# LB_BIT_o13_FAN-v03_rev4_4.net
KiCad netlist of a schematic drawn in EAGLE
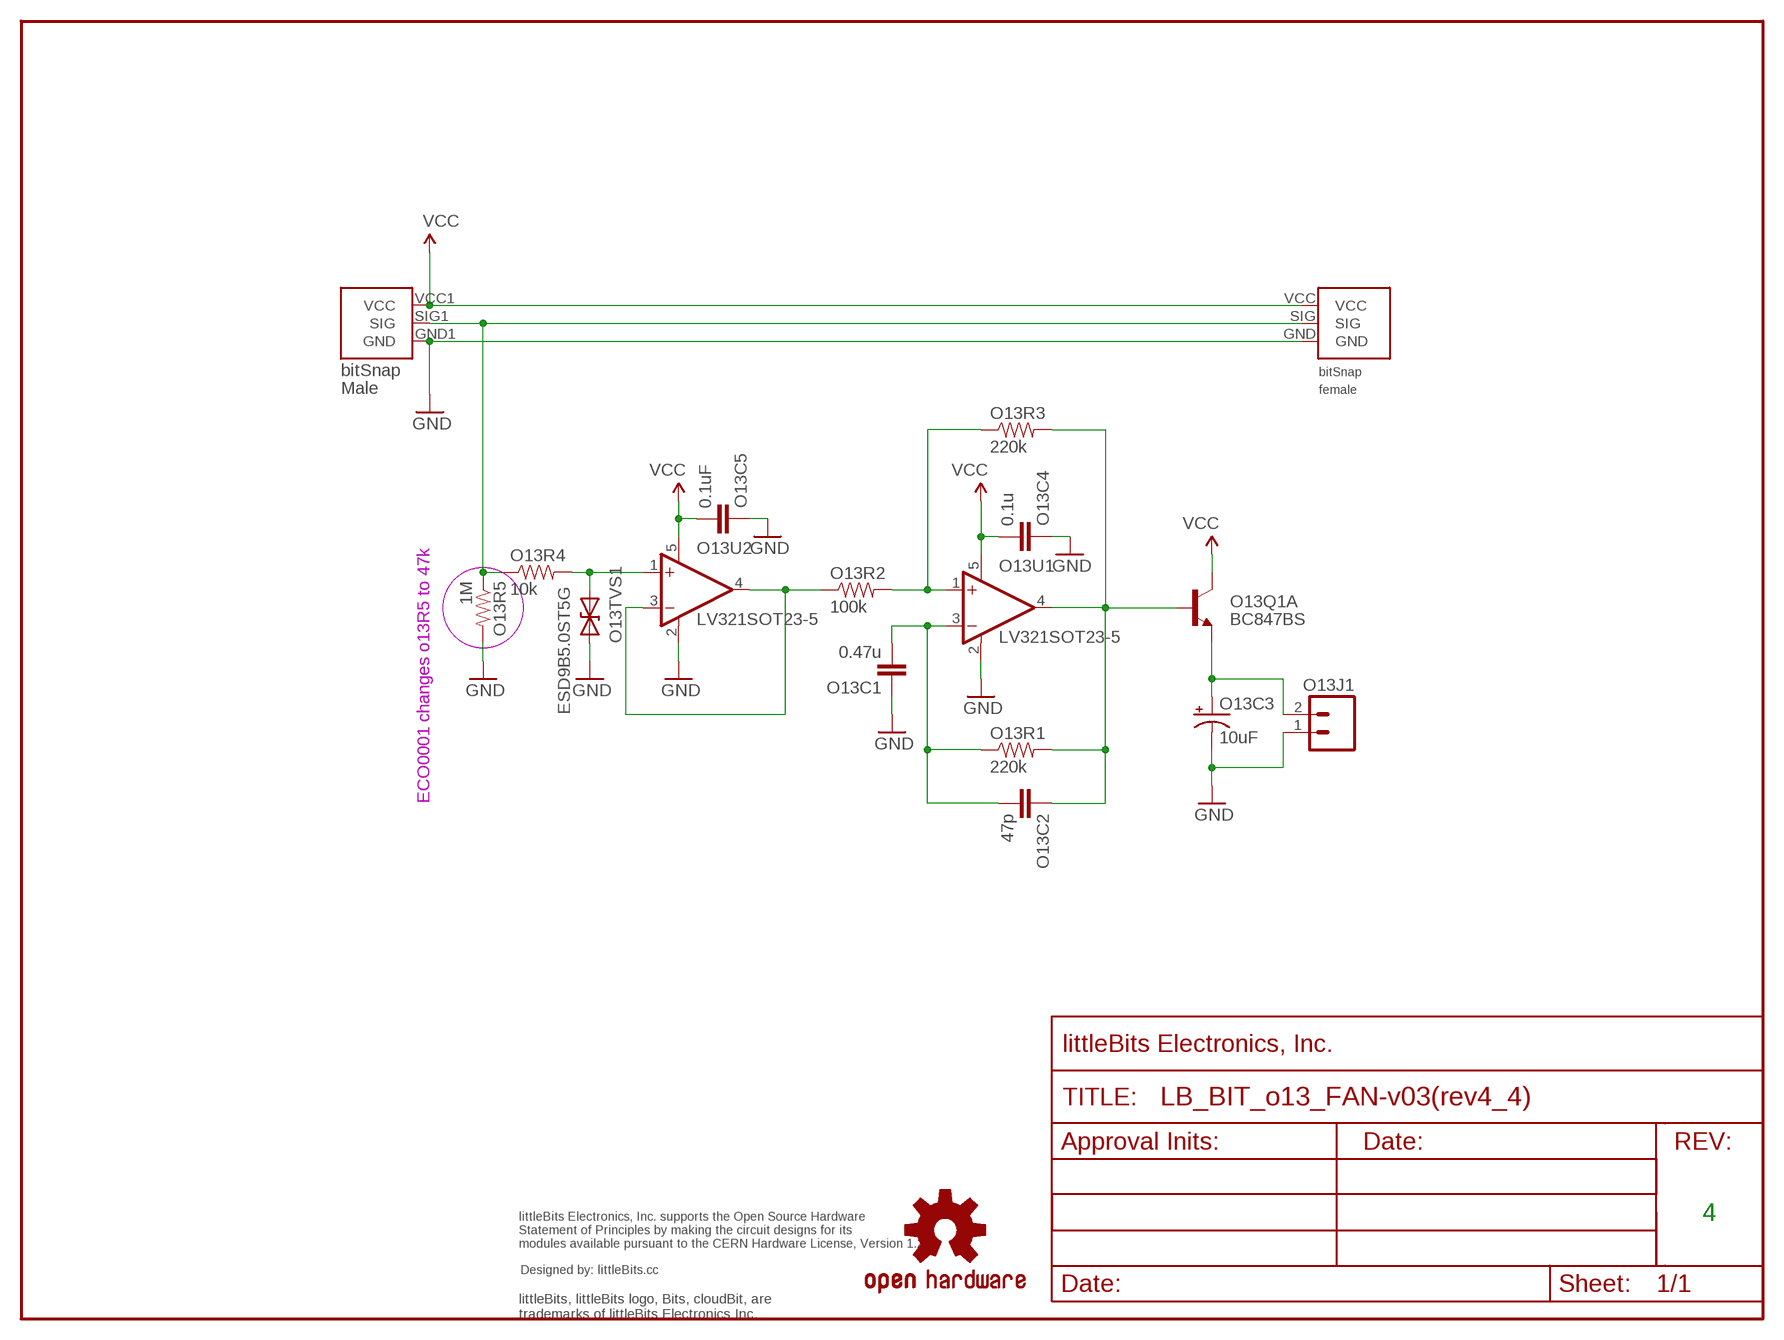
[diagram p0: schematic, sheet 1]

(export (version "E")
  (design (tool "Eeschema 10.0.6"))
  (components
    (comp (ref "O13BSF1")
      (value "BITSNAP_V03_FEMALE")
      (footprint "eagle-import:BITSNAP_V03_FEMALE")
      (libsource (lib "eagle-import") (part "BITSNAP_V03_FEMALE"))
    )
    (comp (ref "O13BSM1")
      (value "BITSNAP_V03_MALE")
      (footprint "eagle-import:BITSNAP_V03_MALE")
      (libsource (lib "eagle-import") (part "BITSNAP_V03_MALE"))
    )
    (comp (ref "O13C1")
      (value "0.47u")
      (footprint "eagle-import:CAP-0603")
      (libsource (lib "eagle-import") (part "CAPCAP-0603"))
    )
    (comp (ref "O13C2")
      (value "47p")
      (footprint "eagle-import:CAP-0603")
      (libsource (lib "eagle-import") (part "CAPCAP-0603"))
    )
    (comp (ref "O13C3")
      (value "10uF")
      (footprint "eagle-import:EIA3216")
      (libsource (lib "eagle-import") (part "CAP_POL3216"))
    )
    (comp (ref "O13C4")
      (value "0.1u")
      (footprint "eagle-import:CAP-0603")
      (libsource (lib "eagle-import") (part "CAPCAP-0603"))
    )
    (comp (ref "O13C5")
      (value "0.1uF")
      (footprint "eagle-import:CAP-0603")
      (libsource (lib "eagle-import") (part "CAPCAP-0603"))
    )
    (comp (ref "O13J1")
      (value "HDR-2JST-2-SMD")
      (footprint "eagle-import:JST-2-SMD")
      (libsource (lib "eagle-import") (part "HDR-2JST-2-SMD"))
    )
    (comp (ref "O13Q1")
      (value "BC847BS")
      (footprint "eagle-import:SOT-363_PHILLIPS")
      (libsource (lib "eagle-import") (part "TRANS-BJT_NPN-DUAL-BC847BS"))
    )
    (comp (ref "O13R1")
      (value "220k")
      (footprint "eagle-import:RES-0603")
      (libsource (lib "eagle-import") (part "RESISTOR0603"))
    )
    (comp (ref "O13R2")
      (value "100k")
      (footprint "eagle-import:RES-0603")
      (libsource (lib "eagle-import") (part "RESISTOR0603"))
    )
    (comp (ref "O13R3")
      (value "220k")
      (footprint "eagle-import:RES-0603")
      (libsource (lib "eagle-import") (part "RESISTOR0603"))
    )
    (comp (ref "O13R4")
      (value "10k")
      (footprint "eagle-import:RES-0603")
      (libsource (lib "eagle-import") (part "RESISTOR0603"))
    )
    (comp (ref "O13R5")
      (value "1M")
      (footprint "eagle-import:RES-0603")
      (libsource (lib "eagle-import") (part "RESISTOR0603"))
    )
    (comp (ref "O13TVS1")
      (value "ESD9B5.0ST5G")
      (footprint "eagle-import:SOD-923")
      (libsource (lib "eagle-import") (part "DIODE-TVSSOD-923"))
    )
    (comp (ref "O13U1")
      (value "LV321SOT23-5")
      (footprint "eagle-import:SOT23-5")
      (libsource (lib "eagle-import") (part "LV321SOT23-5"))
    )
    (comp (ref "O13U2")
      (value "LV321SOT23-5")
      (footprint "eagle-import:SOT23-5")
      (libsource (lib "eagle-import") (part "LV321SOT23-5"))
    )
    (comp (ref "U$1")
      (value "OSHWCREDIT")
      (footprint "eagle-import:OSHWCREDIT")
      (libsource (lib "eagle-import") (part "OSHWCREDIT"))
    )
    (comp (ref "U$2")
      (value "FRAME-LETTER-OHWOHW")
      (footprint "eagle-import:FABDWG01-OHW")
      (libsource (lib "eagle-import") (part "FRAME-LETTER-OHWOHW"))
    )
    (comp (ref "U$3")
      (value "OSHW-LOGOL")
      (footprint "eagle-import:OSHW-LOGO-L")
      (libsource (lib "eagle-import") (part "OSHW-LOGOL"))
    )
  )
  (nets
    (net (code "1") (name "GND") (class "Default")
      (node (ref "O13BSF1") (pin "GND") (pinfunction "GND_GND") (pintype "bidirectional"))
      (node (ref "O13BSM1") (pin "GND1") (pinfunction "GND_GND1") (pintype "bidirectional"))
      (node (ref "O13C1") (pin "1") (pinfunction "1_1") (pintype "passive"))
      (node (ref "O13C3") (pin "-") (pinfunction "-_-") (pintype "passive"))
      (node (ref "O13C4") (pin "1") (pinfunction "1_1") (pintype "passive"))
      (node (ref "O13C5") (pin "1") (pinfunction "1_1") (pintype "passive"))
      (node (ref "O13J1") (pin "1") (pinfunction "1_1") (pintype "passive"))
      (node (ref "O13R5") (pin "2") (pinfunction "2_2") (pintype "passive"))
      (node (ref "O13TVS1") (pin "1") (pinfunction "A_1") (pintype "passive"))
      (node (ref "O13U1") (pin "2") (pinfunction "V-_2") (pintype "power_in"))
      (node (ref "O13U2") (pin "2") (pinfunction "V-_2") (pintype "power_in"))
    )
    (net (code "2") (name "Net-(O13BSM1-SIG)") (class "Default")
      (node (ref "O13BSF1") (pin "SIG") (pinfunction "SIG_SIG") (pintype "bidirectional"))
      (node (ref "O13BSM1") (pin "SIG1") (pinfunction "SIG_SIG1") (pintype "bidirectional"))
      (node (ref "O13R4") (pin "1") (pinfunction "1_1") (pintype "passive"))
      (node (ref "O13R5") (pin "1") (pinfunction "1_1") (pintype "passive"))
    )
    (net (code "3") (name "Net-(O13Q1A-B)") (class "Default")
      (node (ref "O13C2") (pin "1") (pinfunction "1_1") (pintype "passive"))
      (node (ref "O13Q1") (pin "2") (pinfunction "B_2") (pintype "passive"))
      (node (ref "O13R1") (pin "2") (pinfunction "2_2") (pintype "passive"))
      (node (ref "O13R3") (pin "2") (pinfunction "2_2") (pintype "passive"))
      (node (ref "O13U1") (pin "4") (pinfunction "OUT_4") (pintype "output"))
    )
    (net (code "4") (name "Net-(O13Q1A-E)") (class "Default")
      (node (ref "O13C3") (pin "+") (pinfunction "+_+") (pintype "passive"))
      (node (ref "O13J1") (pin "2") (pinfunction "2_2") (pintype "passive"))
      (node (ref "O13Q1") (pin "1") (pinfunction "E_1") (pintype "passive"))
    )
    (net (code "5") (name "Net-(O13TVS1-C)") (class "Default")
      (node (ref "O13R4") (pin "2") (pinfunction "2_2") (pintype "passive"))
      (node (ref "O13TVS1") (pin "2") (pinfunction "C_2") (pintype "passive"))
      (node (ref "O13U2") (pin "1") (pinfunction "+IN_1") (pintype "input"))
    )
    (net (code "6") (name "Net-(O13U1-+IN)") (class "Default")
      (node (ref "O13R2") (pin "2") (pinfunction "2_2") (pintype "passive"))
      (node (ref "O13R3") (pin "1") (pinfunction "1_1") (pintype "passive"))
      (node (ref "O13U1") (pin "1") (pinfunction "+IN_1") (pintype "input"))
    )
    (net (code "7") (name "Net-(O13U1--IN)") (class "Default")
      (node (ref "O13C1") (pin "2") (pinfunction "2_2") (pintype "passive"))
      (node (ref "O13C2") (pin "2") (pinfunction "2_2") (pintype "passive"))
      (node (ref "O13R1") (pin "1") (pinfunction "1_1") (pintype "passive"))
      (node (ref "O13U1") (pin "3") (pinfunction "-IN_3") (pintype "input"))
    )
    (net (code "8") (name "Net-(O13U2--IN)") (class "Default")
      (node (ref "O13R2") (pin "1") (pinfunction "1_1") (pintype "passive"))
      (node (ref "O13U2") (pin "3") (pinfunction "-IN_3") (pintype "input"))
      (node (ref "O13U2") (pin "4") (pinfunction "OUT_4") (pintype "output"))
    )
    (net (code "9") (name "VCC") (class "Default")
      (node (ref "O13BSF1") (pin "VCC") (pinfunction "VCC_VCC") (pintype "bidirectional"))
      (node (ref "O13BSM1") (pin "VCC1") (pinfunction "VCC_VCC1") (pintype "bidirectional"))
      (node (ref "O13C4") (pin "2") (pinfunction "2_2") (pintype "passive"))
      (node (ref "O13C5") (pin "2") (pinfunction "2_2") (pintype "passive"))
      (node (ref "O13Q1") (pin "6") (pinfunction "C_6") (pintype "passive"))
      (node (ref "O13U1") (pin "5") (pinfunction "V+_5") (pintype "power_in"))
      (node (ref "O13U2") (pin "5") (pinfunction "V+_5") (pintype "power_in"))
    )
  )
)
